# G2G-X_Module.net
KiCad netlist of a schematic drawn in Altium Designer
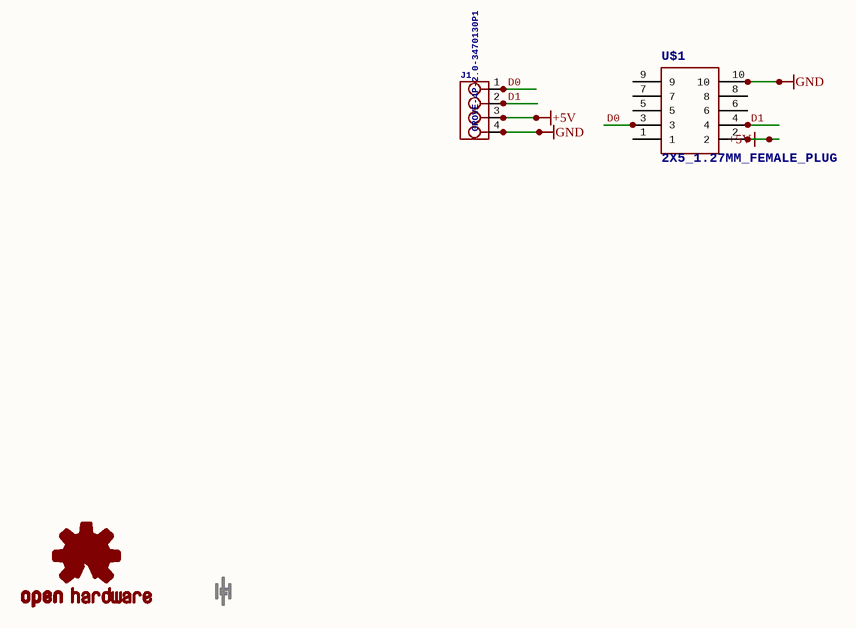
[diagram p0: G2G-X Module.SchDoc]

(export (version "E")
  (design (tool "Eeschema 10.0.6"))
  (components
    (comp (ref "J1")
      (value "GROVE-4P-2.0-3470130P1")
      (footprint "4P-2.0")
      (fields (field (name ">NAME") "J1") (field (name ">VALUE") "GROVE-4P-2.0-3470130P1"))
      (libsource (lib "SoftDust") (part "GROVE-4P-2.0-3470130P1"))
    )
    (comp (ref "LOGO1")
      (value "OSHW-LOGOS")
      (footprint "OSHW-LOGO-S")
      (libsource (lib "SparkFun-Aesthetics") (part "OSHW-LOGOS"))
    )
    (comp (ref "U$1")
      (value "2X5_1.27MM_FEMALE_PLUG")
      (footprint "2X5_1.27MM_FEMALE_PLUG")
      (fields (field (name ">NAME") "U$1") (field (name ">VALUE") "2X5_1.27MM_FEMALE_PLUG"))
      (libsource (lib "SoftDust") (part "2X5_1.27MM_FEMALE_PLUG"))
    )
    (comp (ref "U$2")
      (value "GADGETEER_LOGO_SMALL")
      (footprint "GADGETEER_LOGO_SMALL")
      (libsource (lib "SoftDust") (part "GADGETEER_LOGO_SMALL"))
    )
  )
  (nets
    (net (code "1") (name "+5V") (class "Default")
      (node (ref "J1") (pin "3") (pinfunction "3_3") (pintype "passive"))
      (node (ref "U$1") (pin "2") (pinfunction "2_2") (pintype "passive"))
    )
    (net (code "2") (name "/D0") (class "Default")
      (node (ref "J1") (pin "1") (pinfunction "1_1") (pintype "passive"))
      (node (ref "U$1") (pin "3") (pinfunction "3_3") (pintype "passive"))
    )
    (net (code "3") (name "/D1") (class "Default")
      (node (ref "J1") (pin "2") (pinfunction "2_2") (pintype "passive"))
      (node (ref "U$1") (pin "4") (pinfunction "4_4") (pintype "passive"))
    )
    (net (code "4") (name "GND") (class "Default")
      (node (ref "J1") (pin "4") (pinfunction "4_4") (pintype "passive"))
      (node (ref "U$1") (pin "10") (pinfunction "10_10") (pintype "passive"))
    )
    (net (code "5") (name "unconnected-(U$1-Pad1)") (class "Default")
      (node (ref "U$1") (pin "1") (pinfunction "1_1") (pintype "passive"))
    )
    (net (code "6") (name "unconnected-(U$1-Pad5)") (class "Default")
      (node (ref "U$1") (pin "5") (pinfunction "5_5") (pintype "passive"))
    )
    (net (code "7") (name "unconnected-(U$1-Pad6)") (class "Default")
      (node (ref "U$1") (pin "6") (pinfunction "6_6") (pintype "passive"))
    )
    (net (code "8") (name "unconnected-(U$1-Pad7)") (class "Default")
      (node (ref "U$1") (pin "7") (pinfunction "7_7") (pintype "passive"))
    )
    (net (code "9") (name "unconnected-(U$1-Pad8)") (class "Default")
      (node (ref "U$1") (pin "8") (pinfunction "8_8") (pintype "passive"))
    )
    (net (code "10") (name "unconnected-(U$1-Pad9)") (class "Default")
      (node (ref "U$1") (pin "9") (pinfunction "9_9") (pintype "passive"))
    )
  )
)
